# current_sense_INA250.net
KiCad netlist of a schematic drawn in EAGLE
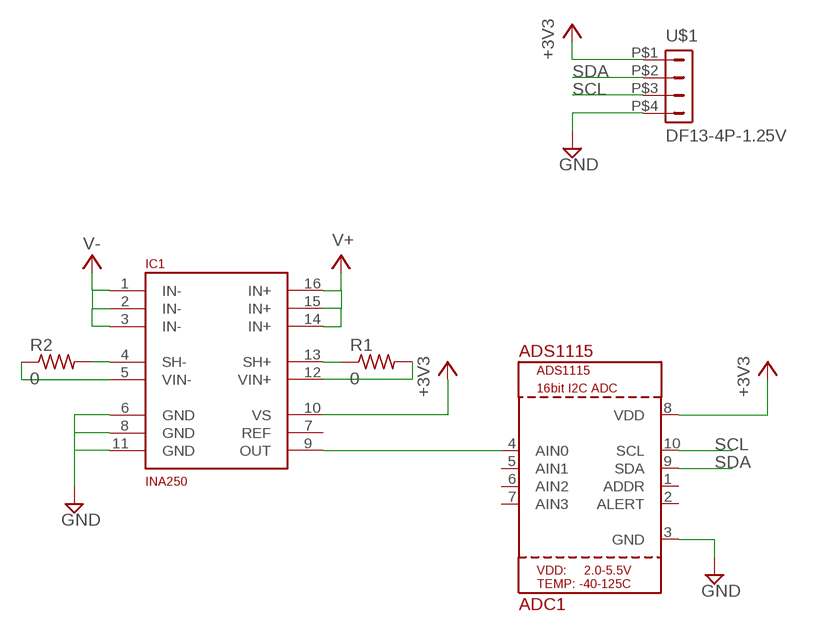
[diagram p0: schematic, sheet 1]

(export (version "E")
  (design (tool "Eeschema 10.0.6"))
  (components
    (comp (ref "ADC1")
      (value "ADS1115")
      (footprint "eagle-import:MSOP10")
      (libsource (lib "eagle-import") (part "ADS1115"))
    )
    (comp (ref "IC1")
      (value "INA250")
      (footprint "eagle-import:TSSOP16")
      (libsource (lib "eagle-import") (part "INA250"))
    )
    (comp (ref "R1")
      (value "0")
      (footprint "eagle-import:R0805")
      (libsource (lib "eagle-import") (part "R-US_R0805"))
    )
    (comp (ref "R2")
      (value "0")
      (footprint "eagle-import:R0805")
      (libsource (lib "eagle-import") (part "R-US_R0805"))
    )
    (comp (ref "U$1")
      (value "DF13-4P-1.25V")
      (footprint "eagle-import:DF13C-4P-1.25V")
      (libsource (lib "eagle-import") (part "DF13-4P-1.25V"))
    )
  )
  (nets
    (net (code "1") (name "+3V3") (class "Default")
      (node (ref "ADC1") (pin "8") (pinfunction "VDD_8") (pintype "bidirectional"))
      (node (ref "IC1") (pin "10") (pinfunction "VS_10") (pintype "bidirectional"))
      (node (ref "U$1") (pin "P$1") (pinfunction "1_P$1") (pintype "passive"))
    )
    (net (code "2") (name "/SCL") (class "Default")
      (node (ref "ADC1") (pin "10") (pinfunction "SCL_10") (pintype "bidirectional"))
      (node (ref "U$1") (pin "P$3") (pinfunction "3_P$3") (pintype "passive"))
    )
    (net (code "3") (name "/SDA") (class "Default")
      (node (ref "ADC1") (pin "9") (pinfunction "SDA_9") (pintype "bidirectional"))
      (node (ref "U$1") (pin "P$2") (pinfunction "2_P$2") (pintype "passive"))
    )
    (net (code "4") (name "GND") (class "Default")
      (node (ref "ADC1") (pin "3") (pinfunction "GND_3") (pintype "bidirectional"))
      (node (ref "IC1") (pin "11") (pinfunction "GND_11") (pintype "bidirectional"))
      (node (ref "IC1") (pin "6") (pinfunction "GND_6") (pintype "bidirectional"))
      (node (ref "IC1") (pin "8") (pinfunction "GND_8") (pintype "bidirectional"))
      (node (ref "U$1") (pin "P$4") (pinfunction "4_P$4") (pintype "passive"))
    )
    (net (code "5") (name "Net-(ADC1-AIN0)") (class "Default")
      (node (ref "ADC1") (pin "4") (pinfunction "AIN0_4") (pintype "bidirectional"))
      (node (ref "IC1") (pin "9") (pinfunction "OUT_9") (pintype "bidirectional"))
    )
    (net (code "6") (name "Net-(IC1-SH+)") (class "Default")
      (node (ref "IC1") (pin "13") (pinfunction "SH+_13") (pintype "bidirectional"))
      (node (ref "R1") (pin "1") (pinfunction "1_1") (pintype "passive"))
    )
    (net (code "7") (name "Net-(IC1-SH-)") (class "Default")
      (node (ref "IC1") (pin "4") (pinfunction "SH-_4") (pintype "bidirectional"))
      (node (ref "R2") (pin "2") (pinfunction "2_2") (pintype "passive"))
    )
    (net (code "8") (name "Net-(IC1-VIN+)") (class "Default")
      (node (ref "IC1") (pin "12") (pinfunction "VIN+_12") (pintype "bidirectional"))
      (node (ref "R1") (pin "2") (pinfunction "2_2") (pintype "passive"))
    )
    (net (code "9") (name "Net-(IC1-VIN-)") (class "Default")
      (node (ref "IC1") (pin "5") (pinfunction "VIN-_5") (pintype "bidirectional"))
      (node (ref "R2") (pin "1") (pinfunction "1_1") (pintype "passive"))
    )
    (net (code "10") (name "V+") (class "Default")
      (node (ref "IC1") (pin "14") (pinfunction "IN+_14") (pintype "bidirectional"))
      (node (ref "IC1") (pin "15") (pinfunction "IN+_15") (pintype "bidirectional"))
      (node (ref "IC1") (pin "16") (pinfunction "IN+_16") (pintype "bidirectional"))
    )
    (net (code "11") (name "V-") (class "Default")
      (node (ref "IC1") (pin "1") (pinfunction "IN-_1") (pintype "bidirectional"))
      (node (ref "IC1") (pin "2") (pinfunction "IN-_2") (pintype "bidirectional"))
      (node (ref "IC1") (pin "3") (pinfunction "IN-_3") (pintype "bidirectional"))
    )
    (net (code "12") (name "unconnected-(ADC1-ADDR-Pad1)") (class "Default")
      (node (ref "ADC1") (pin "1") (pinfunction "ADDR_1") (pintype "bidirectional"))
    )
    (net (code "13") (name "unconnected-(ADC1-AIN1-Pad5)") (class "Default")
      (node (ref "ADC1") (pin "5") (pinfunction "AIN1_5") (pintype "bidirectional"))
    )
    (net (code "14") (name "unconnected-(ADC1-AIN2-Pad6)") (class "Default")
      (node (ref "ADC1") (pin "6") (pinfunction "AIN2_6") (pintype "bidirectional"))
    )
    (net (code "15") (name "unconnected-(ADC1-AIN3-Pad7)") (class "Default")
      (node (ref "ADC1") (pin "7") (pinfunction "AIN3_7") (pintype "bidirectional"))
    )
    (net (code "16") (name "unconnected-(ADC1-ALERT-Pad2)") (class "Default")
      (node (ref "ADC1") (pin "2") (pinfunction "ALERT_2") (pintype "bidirectional"))
    )
    (net (code "17") (name "unconnected-(IC1-REF-Pad7)") (class "Default")
      (node (ref "IC1") (pin "7") (pinfunction "REF_7") (pintype "bidirectional"))
    )
  )
)
